# mbed_6LoWPAN_Border_Router_HAT.net
KiCad netlist of a schematic drawn in EAGLE
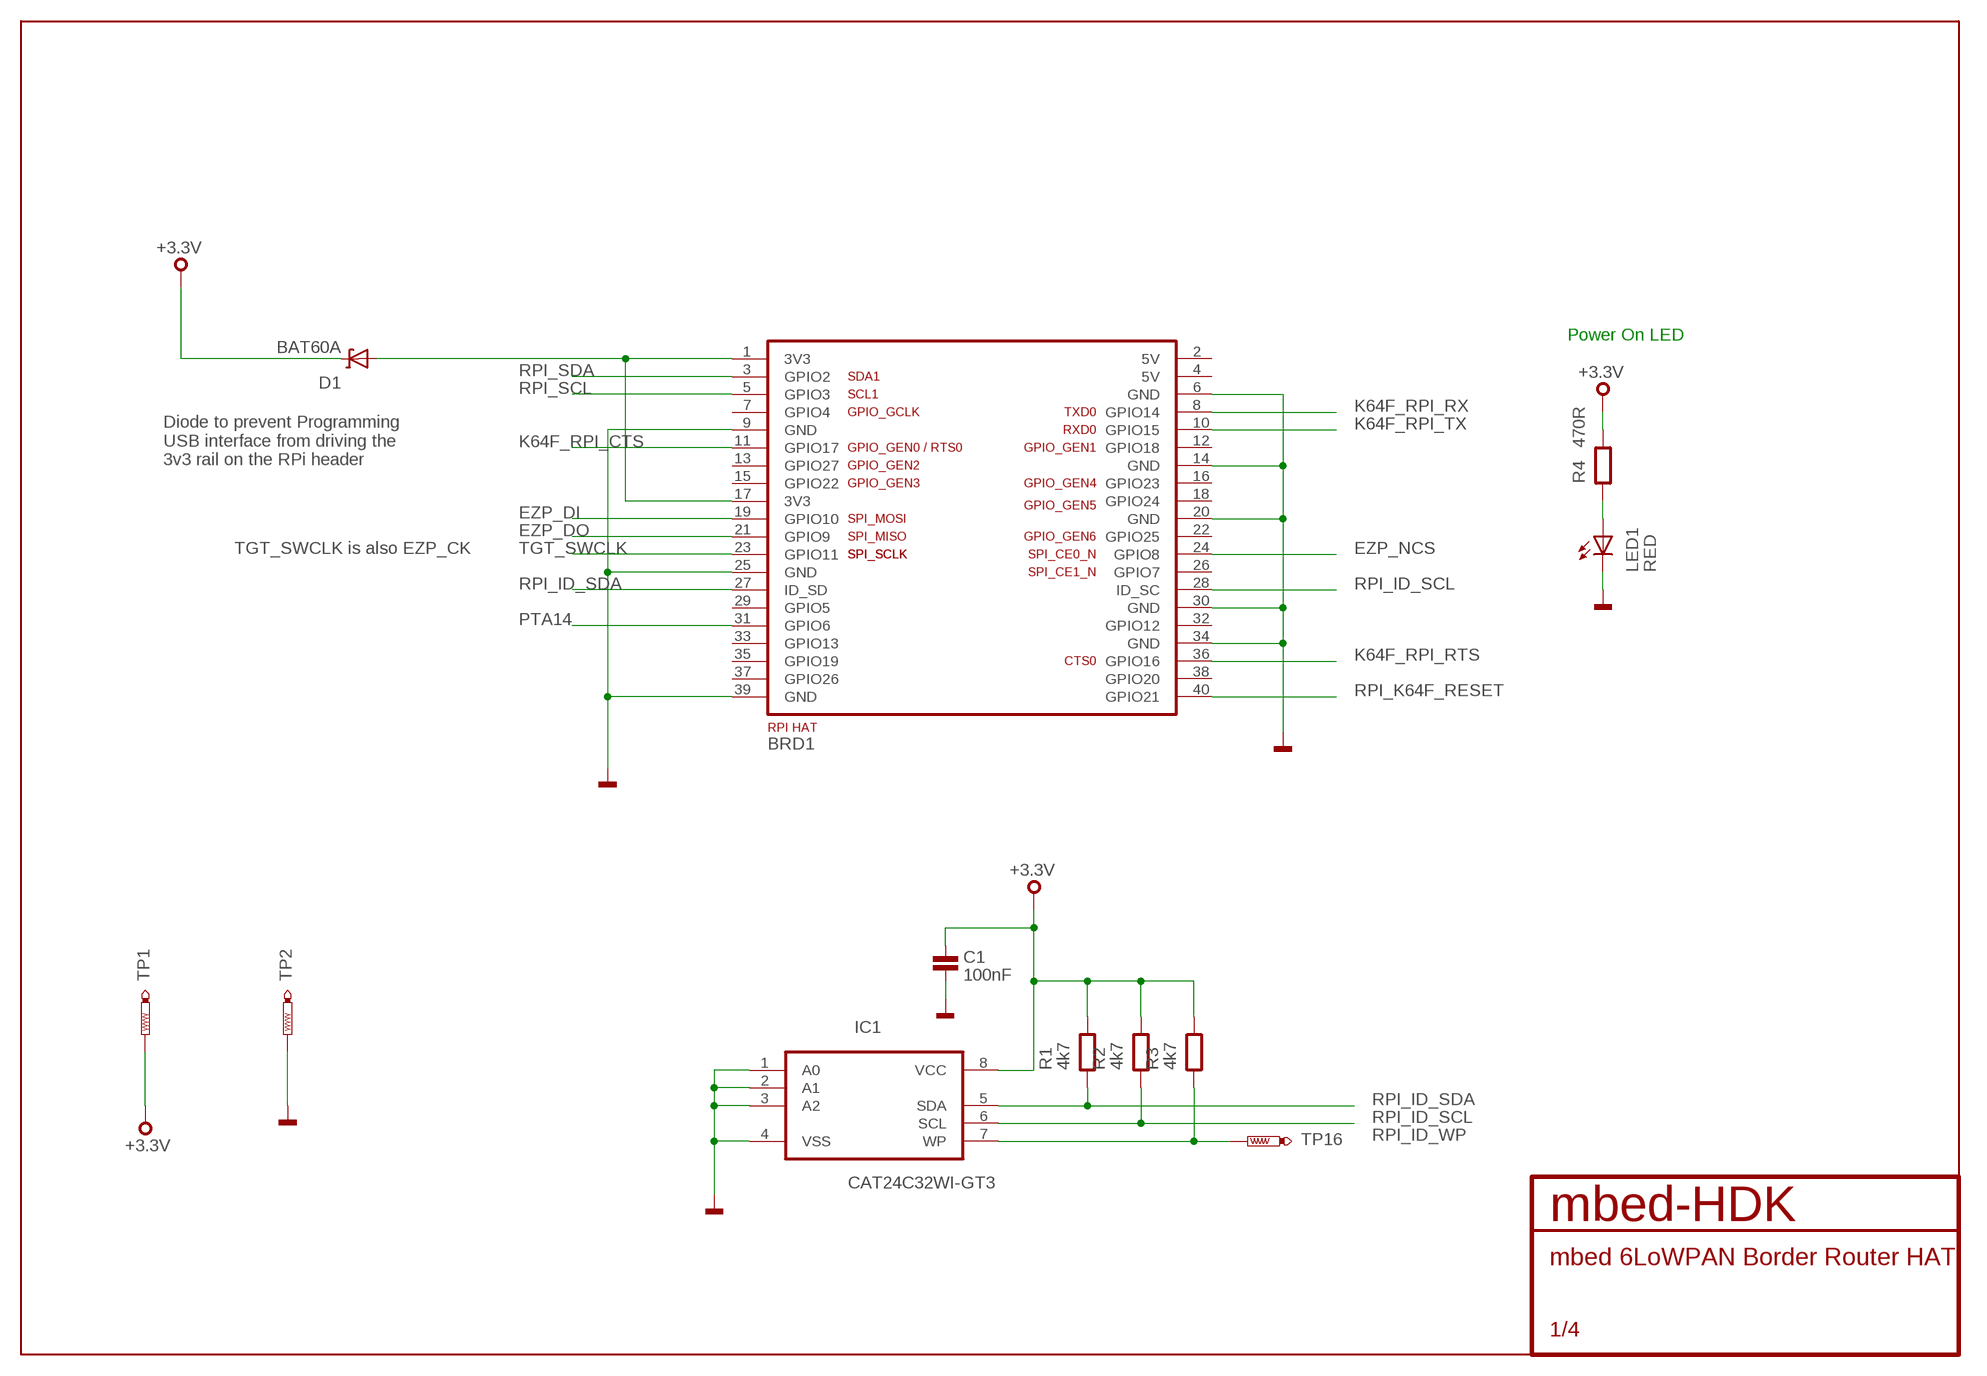
[diagram p0: schematic, sheet 1]
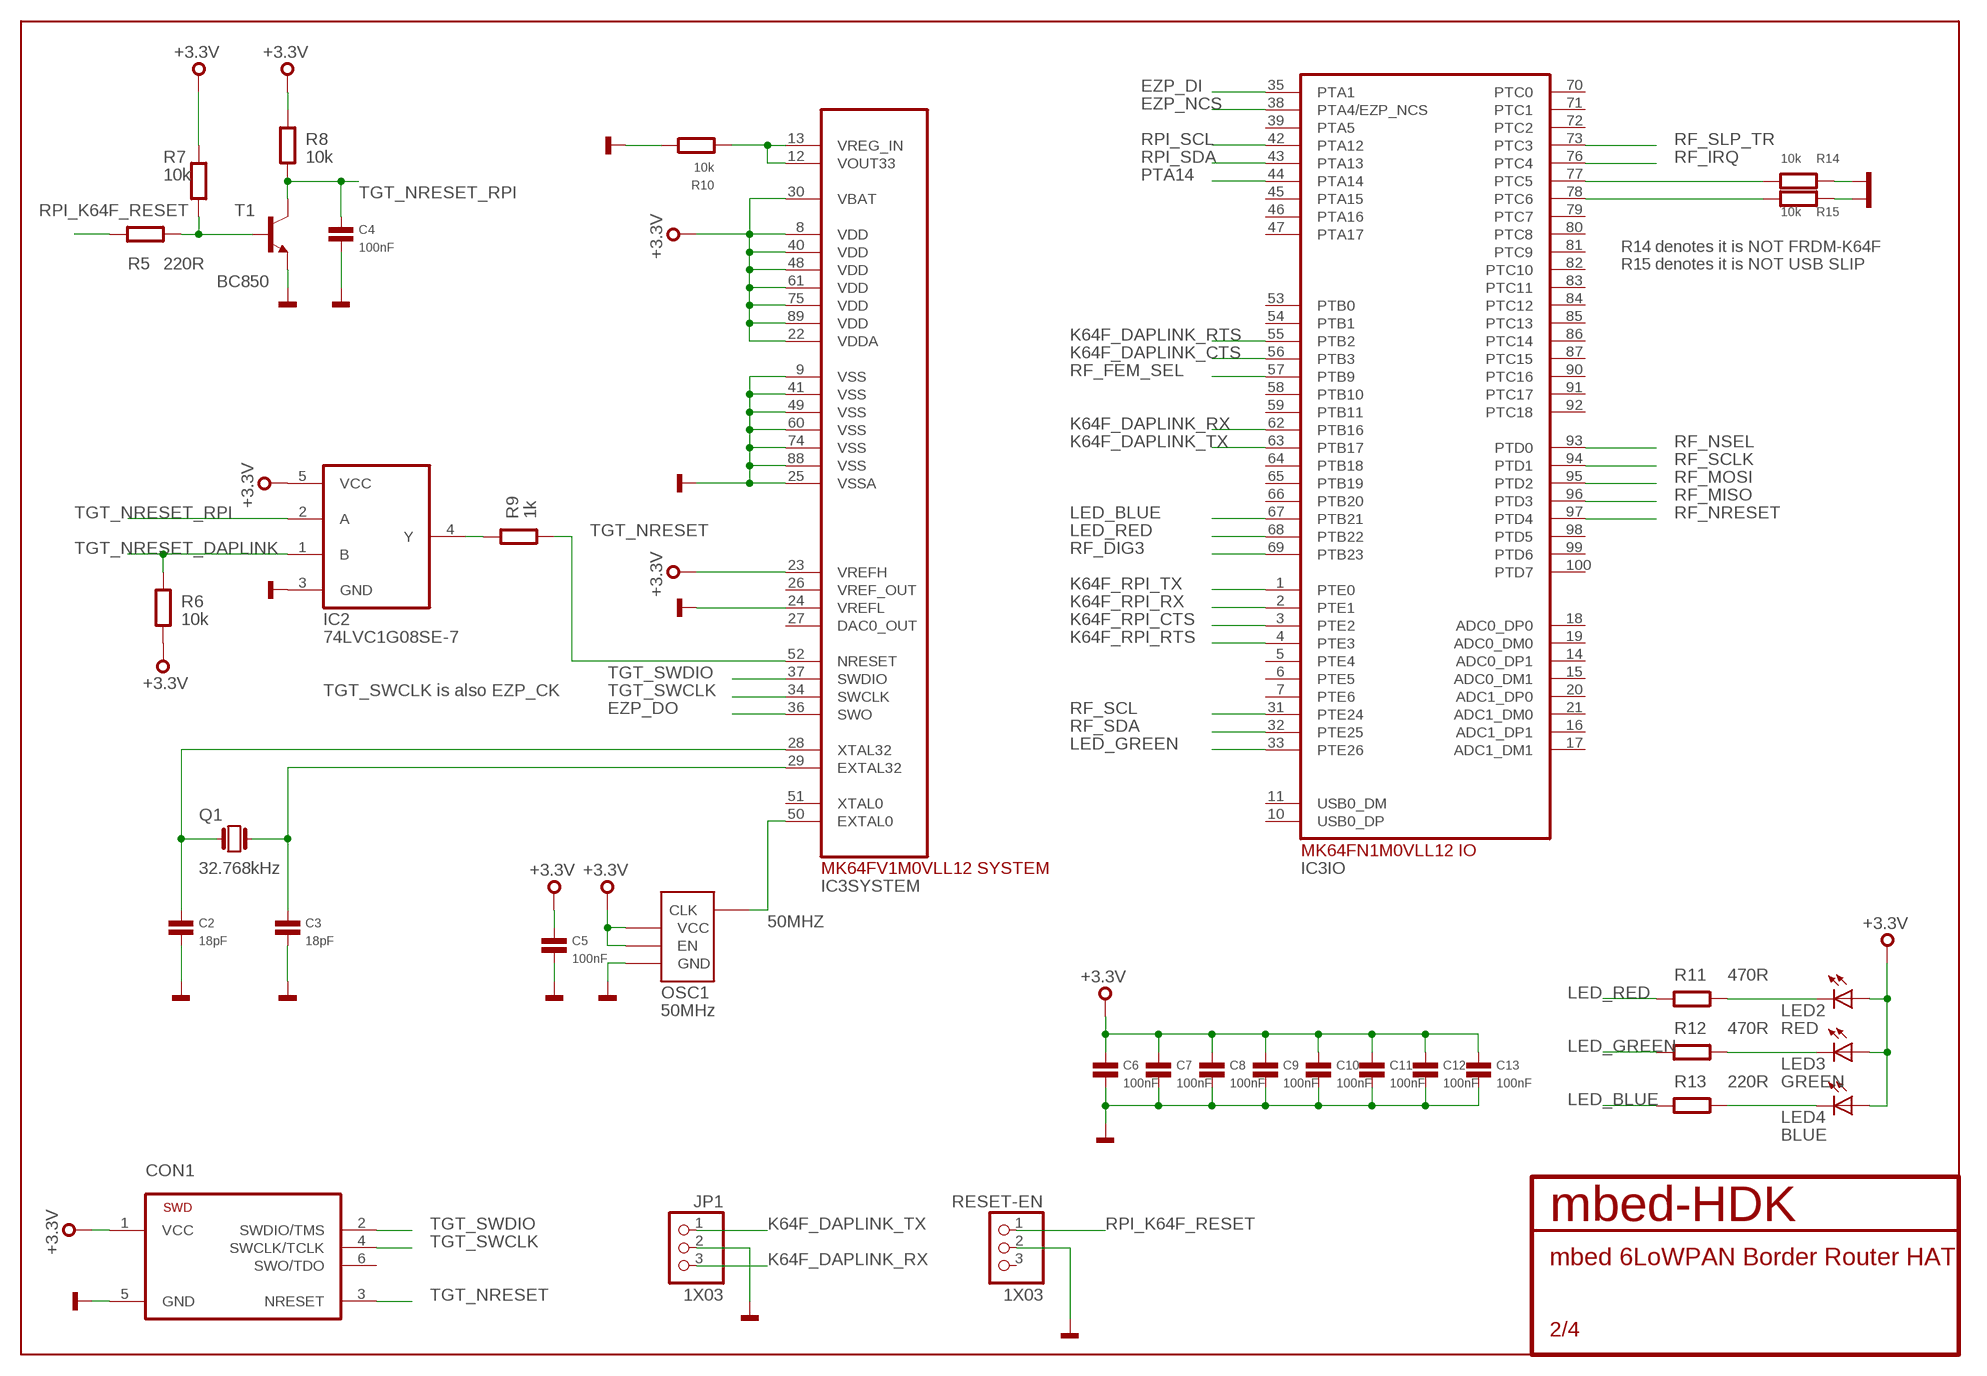
[diagram p1: schematic, sheet 2]
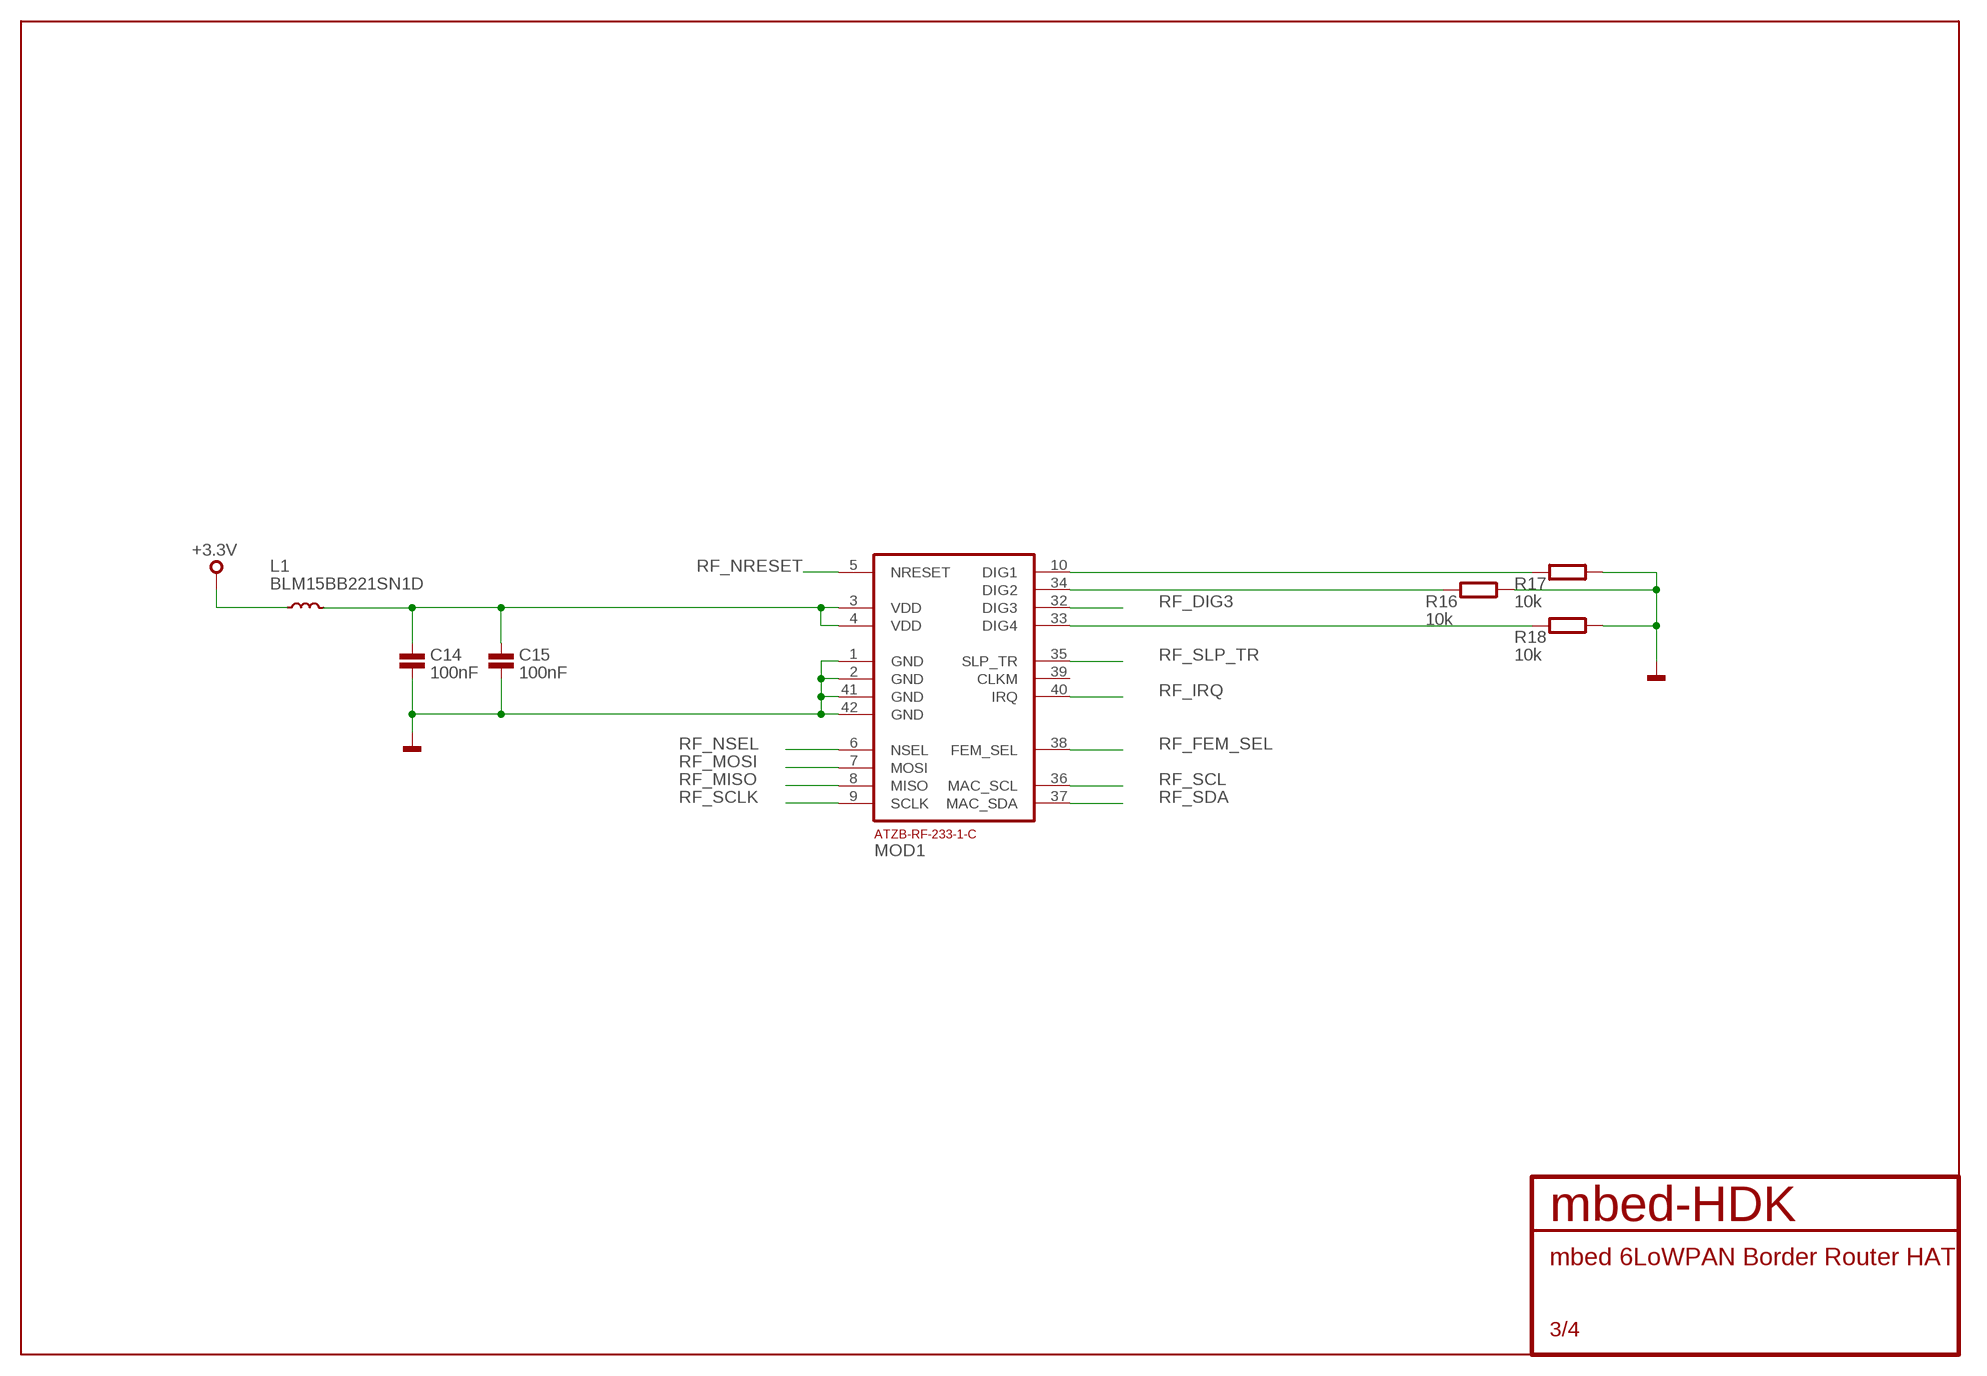
[diagram p2: schematic, sheet 3]
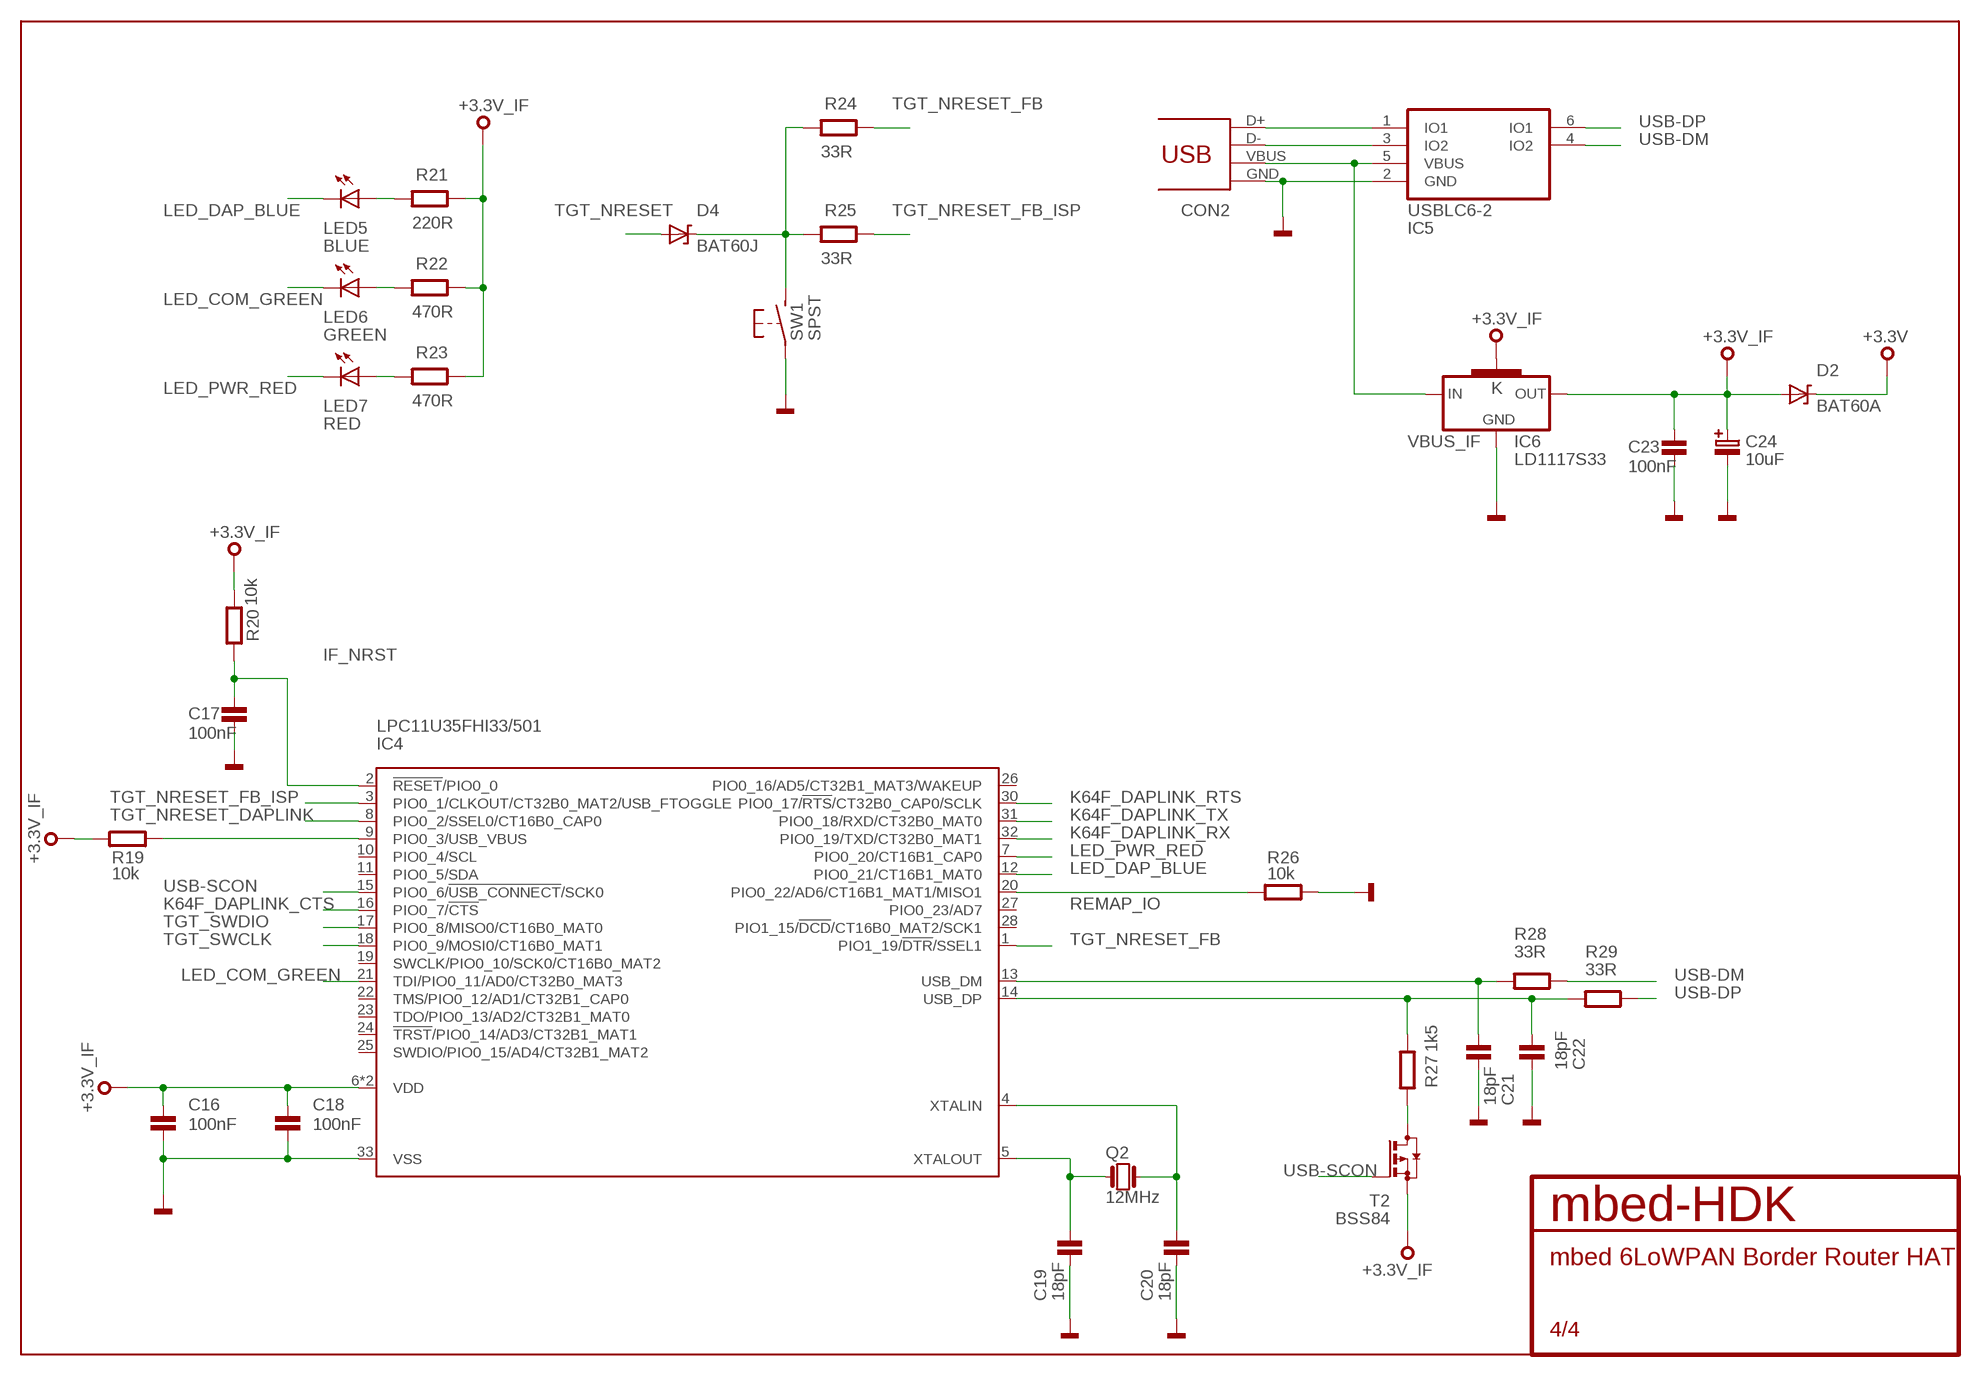
[diagram p3: schematic, sheet 4]

(export (version "E")
  (design (tool "Eeschema 10.0.6"))
  (components
    (comp (ref "C2")
      (value "18pF")
      (footprint "eagle-import:0402")
      (libsource (lib "eagle-import") (part "C0402"))
    )
    (comp (ref "C3")
      (value "18pF")
      (footprint "eagle-import:0402")
      (libsource (lib "eagle-import") (part "C0402"))
    )
    (comp (ref "C4")
      (value "100nF")
      (footprint "eagle-import:0402")
      (libsource (lib "eagle-import") (part "C0402"))
    )
    (comp (ref "C5")
      (value "100nF")
      (footprint "eagle-import:0402")
      (libsource (lib "eagle-import") (part "C0402"))
    )
    (comp (ref "C6")
      (value "100nF")
      (footprint "eagle-import:0402")
      (libsource (lib "eagle-import") (part "C0402"))
    )
    (comp (ref "C7")
      (value "100nF")
      (footprint "eagle-import:0402")
      (libsource (lib "eagle-import") (part "C0402"))
    )
    (comp (ref "C8")
      (value "100nF")
      (footprint "eagle-import:0402")
      (libsource (lib "eagle-import") (part "C0402"))
    )
    (comp (ref "C9")
      (value "100nF")
      (footprint "eagle-import:0402")
      (libsource (lib "eagle-import") (part "C0402"))
    )
    (comp (ref "C10")
      (value "100nF")
      (footprint "eagle-import:0402")
      (libsource (lib "eagle-import") (part "C0402"))
    )
    (comp (ref "C11")
      (value "100nF")
      (footprint "eagle-import:0402")
      (libsource (lib "eagle-import") (part "C0402"))
    )
    (comp (ref "C12")
      (value "100nF")
      (footprint "eagle-import:0402")
      (libsource (lib "eagle-import") (part "C0402"))
    )
    (comp (ref "C13")
      (value "100nF")
      (footprint "eagle-import:0402")
      (libsource (lib "eagle-import") (part "C0402"))
    )
    (comp (ref "CON1")
      (value "TC2030-CTX-NL")
      (footprint "eagle-import:TC2030-CTX-NL")
      (libsource (lib "eagle-import") (part "TC2030-CTX-NL"))
    )
    (comp (ref "IC2")
      (value "74LVC1G08SE-7")
      (footprint "eagle-import:SOT353")
      (fields (field (name "MF") "Diodes Inc."))
      (libsource (lib "eagle-import") (part "74LVC1GXX"))
    )
    (comp (ref "IC3")
      (value "MK64FN1M0VLL12")
      (footprint "eagle-import:LQFP100")
      (libsource (lib "eagle-import") (part "MK64FN1M0VLL12"))
    )
    (comp (ref "JP1")
      (value "1X03")
      (footprint "eagle-import:1X03")
      (libsource (lib "eagle-import") (part "PINHD-1X3"))
    )
    (comp (ref "LED2")
      (value "RED")
      (footprint "eagle-import:CHIPLED_0603")
      (libsource (lib "eagle-import") (part "LED0603"))
    )
    (comp (ref "LED3")
      (value "GREEN")
      (footprint "eagle-import:CHIPLED_0603")
      (libsource (lib "eagle-import") (part "LED0603"))
    )
    (comp (ref "LED4")
      (value "BLUE")
      (footprint "eagle-import:CHIPLED_0603")
      (libsource (lib "eagle-import") (part "LED0603"))
    )
    (comp (ref "OSC1")
      (value "50MHz")
      (footprint "eagle-import:3.2X.2.5")
      (libsource (lib "eagle-import") (part "OSCILLATOR3.2X2.5"))
    )
    (comp (ref "Q1")
      (value "32.768kHz")
      (footprint "eagle-import:FC135")
      (libsource (lib "eagle-import") (part "Q_FC135"))
    )
    (comp (ref "R5")
      (value "220R")
      (footprint "eagle-import:0402")
      (libsource (lib "eagle-import") (part "R0402"))
    )
    (comp (ref "R6")
      (value "10k")
      (footprint "eagle-import:0402")
      (libsource (lib "eagle-import") (part "R0402"))
    )
    (comp (ref "R7")
      (value "10k")
      (footprint "eagle-import:0402")
      (libsource (lib "eagle-import") (part "R0402"))
    )
    (comp (ref "R8")
      (value "10k")
      (footprint "eagle-import:0402")
      (libsource (lib "eagle-import") (part "R0402"))
    )
    (comp (ref "R9")
      (value "1k")
      (footprint "eagle-import:0402")
      (libsource (lib "eagle-import") (part "R0402"))
    )
    (comp (ref "R10")
      (value "10k")
      (footprint "eagle-import:0402")
      (libsource (lib "eagle-import") (part "R0402"))
    )
    (comp (ref "R11")
      (value "470R")
      (footprint "eagle-import:0402")
      (libsource (lib "eagle-import") (part "R0402"))
    )
    (comp (ref "R12")
      (value "470R")
      (footprint "eagle-import:0402")
      (libsource (lib "eagle-import") (part "R0402"))
    )
    (comp (ref "R13")
      (value "220R")
      (footprint "eagle-import:0402")
      (libsource (lib "eagle-import") (part "R0402"))
    )
    (comp (ref "R14")
      (value "10k")
      (footprint "eagle-import:0402")
      (libsource (lib "eagle-import") (part "R0402"))
    )
    (comp (ref "R15")
      (value "10k")
      (footprint "eagle-import:0402")
      (libsource (lib "eagle-import") (part "R0402"))
    )
    (comp (ref "RESET-EN")
      (value "1X03")
      (footprint "eagle-import:1X03")
      (libsource (lib "eagle-import") (part "PINHD-1X3"))
    )
    (comp (ref "T1")
      (value "BC850")
      (footprint "eagle-import:SOT23")
      (libsource (lib "eagle-import") (part "BC850"))
    )
    (comp (ref "BRD1")
      (value "RPI-HAT")
      (footprint "eagle-import:RPI-HAT")
      (libsource (lib "eagle-import") (part "RPI-HAT"))
    )
    (comp (ref "C1")
      (value "100nF")
      (footprint "eagle-import:0402")
      (libsource (lib "eagle-import") (part "C0402"))
    )
    (comp (ref "D1")
      (value "BAT60A")
      (footprint "eagle-import:SOD323")
      (fields (field (name "MF") "Infineon"))
      (libsource (lib "eagle-import") (part "BAT60A"))
    )
    (comp (ref "IC1")
      (value "CAT24C32WI-GT3")
      (footprint "eagle-import:SOIC127P600X175-8N")
      (libsource (lib "eagle-import") (part "CAT24C32WI-GT3"))
    )
    (comp (ref "LED1")
      (value "RED")
      (footprint "eagle-import:CHIPLED_0603")
      (libsource (lib "eagle-import") (part "LED0603"))
    )
    (comp (ref "R1")
      (value "4k7")
      (footprint "eagle-import:0402")
      (libsource (lib "eagle-import") (part "R0402"))
    )
    (comp (ref "R2")
      (value "4k7")
      (footprint "eagle-import:0402")
      (libsource (lib "eagle-import") (part "R0402"))
    )
    (comp (ref "R3")
      (value "4k7")
      (footprint "eagle-import:0402")
      (libsource (lib "eagle-import") (part "R0402"))
    )
    (comp (ref "R4")
      (value "470R")
      (footprint "eagle-import:0402")
      (libsource (lib "eagle-import") (part "R0402"))
    )
    (comp (ref "TP1")
      (value "TEST-POINT-50R-PTH")
      (footprint "eagle-import:TP50-PTH")
      (libsource (lib "eagle-import") (part "TEST-POINT-50R-PTH"))
    )
    (comp (ref "TP2")
      (value "TEST-POINT-50R-PTH")
      (footprint "eagle-import:TP50-PTH")
      (libsource (lib "eagle-import") (part "TEST-POINT-50R-PTH"))
    )
    (comp (ref "TP16")
      (value "TEST-POINT-50R-PTH")
      (footprint "eagle-import:TP50-PTH")
      (libsource (lib "eagle-import") (part "TEST-POINT-50R-PTH"))
    )
    (comp (ref "C14")
      (value "100nF")
      (footprint "eagle-import:0402")
      (libsource (lib "eagle-import") (part "C0402"))
    )
    (comp (ref "C15")
      (value "100nF")
      (footprint "eagle-import:0402")
      (libsource (lib "eagle-import") (part "C0402"))
    )
    (comp (ref "L1")
      (value "BLM15BB221SN1D")
      (footprint "eagle-import:0402")
      (libsource (lib "eagle-import") (part "L0402"))
    )
    (comp (ref "MOD1")
      (value "ATZB-RF-233-1-C")
      (footprint "eagle-import:ATZB-RF-233-1-C")
      (fields (field (name "MF") "Atmel"))
      (libsource (lib "eagle-import") (part "ATZB-RF-233-1-C"))
    )
    (comp (ref "R16")
      (value "10k")
      (footprint "eagle-import:0402")
      (libsource (lib "eagle-import") (part "R0402"))
    )
    (comp (ref "R17")
      (value "10k")
      (footprint "eagle-import:0402")
      (libsource (lib "eagle-import") (part "R0402"))
    )
    (comp (ref "R18")
      (value "10k")
      (footprint "eagle-import:0402")
      (libsource (lib "eagle-import") (part "R0402"))
    )
    (comp (ref "C16")
      (value "100nF")
      (footprint "eagle-import:0402")
      (libsource (lib "eagle-import") (part "C0402"))
    )
    (comp (ref "C17")
      (value "100nF")
      (footprint "eagle-import:0402")
      (libsource (lib "eagle-import") (part "C0402"))
    )
    (comp (ref "C18")
      (value "100nF")
      (footprint "eagle-import:0402")
      (libsource (lib "eagle-import") (part "C0402"))
    )
    (comp (ref "C19")
      (value "18pF")
      (footprint "eagle-import:0402")
      (libsource (lib "eagle-import") (part "C0402"))
    )
    (comp (ref "C20")
      (value "18pF")
      (footprint "eagle-import:0402")
      (libsource (lib "eagle-import") (part "C0402"))
    )
    (comp (ref "C21")
      (value "18pF")
      (footprint "eagle-import:0402")
      (libsource (lib "eagle-import") (part "C0402"))
    )
    (comp (ref "C22")
      (value "18pF")
      (footprint "eagle-import:0402")
      (libsource (lib "eagle-import") (part "C0402"))
    )
    (comp (ref "C23")
      (value "100nF")
      (footprint "eagle-import:0402")
      (libsource (lib "eagle-import") (part "C0402"))
    )
    (comp (ref "C24")
      (value "10uF")
      (footprint "eagle-import:SMC_B")
      (fields (field (name "MF") "Kemet"))
      (libsource (lib "eagle-import") (part "C-POLB"))
    )
    (comp (ref "CON2")
      (value "USB_MICROB")
      (footprint "eagle-import:MOLEX-47364-0001")
      (fields (field (name "MF") "MOLEX"))
      (libsource (lib "eagle-import") (part "USB_MICROB"))
    )
    (comp (ref "D2")
      (value "BAT60A")
      (footprint "eagle-import:SOD323")
      (fields (field (name "MF") "Infineon"))
      (libsource (lib "eagle-import") (part "BAT60A"))
    )
    (comp (ref "D4")
      (value "BAT60J")
      (footprint "eagle-import:SOD323")
      (fields (field (name "MF") "STMicroelectronics"))
      (libsource (lib "eagle-import") (part "BAT60J"))
    )
    (comp (ref "IC4")
      (value "LPC11U35FHI33/501")
      (footprint "eagle-import:SOT617-3")
      (fields (field (name "MF") "NXP Semiconductors"))
      (libsource (lib "eagle-import") (part "LPC11U35FHI33/501"))
    )
    (comp (ref "IC5")
      (value "USBLC6-2SC6")
      (footprint "eagle-import:SOT23-6L")
      (libsource (lib "eagle-import") (part "USBLC6-2SC6"))
    )
    (comp (ref "IC6")
      (value "LD1117S33")
      (footprint "eagle-import:SOT223")
      (libsource (lib "eagle-import") (part "LD1117S33"))
    )
    (comp (ref "LED5")
      (value "BLUE")
      (footprint "eagle-import:CHIPLED_0603")
      (libsource (lib "eagle-import") (part "LED0603"))
    )
    (comp (ref "LED6")
      (value "GREEN")
      (footprint "eagle-import:CHIPLED_0603")
      (libsource (lib "eagle-import") (part "LED0603"))
    )
    (comp (ref "LED7")
      (value "RED")
      (footprint "eagle-import:CHIPLED_0603")
      (libsource (lib "eagle-import") (part "LED0603"))
    )
    (comp (ref "Q2")
      (value "12MHz")
      (footprint "eagle-import:3.2X.2.5")
      (libsource (lib "eagle-import") (part "Q_3.2X2.5"))
    )
    (comp (ref "R19")
      (value "10k")
      (footprint "eagle-import:0402")
      (libsource (lib "eagle-import") (part "R0402"))
    )
    (comp (ref "R20")
      (value "10k")
      (footprint "eagle-import:0402")
      (libsource (lib "eagle-import") (part "R0402"))
    )
    (comp (ref "R21")
      (value "220R")
      (footprint "eagle-import:0402")
      (libsource (lib "eagle-import") (part "R0402"))
    )
    (comp (ref "R22")
      (value "470R")
      (footprint "eagle-import:0402")
      (libsource (lib "eagle-import") (part "R0402"))
    )
    (comp (ref "R23")
      (value "470R")
      (footprint "eagle-import:0402")
      (libsource (lib "eagle-import") (part "R0402"))
    )
    (comp (ref "R24")
      (value "33R")
      (footprint "eagle-import:0402")
      (libsource (lib "eagle-import") (part "R0402"))
    )
    (comp (ref "R25")
      (value "33R")
      (footprint "eagle-import:0402")
      (libsource (lib "eagle-import") (part "R0402"))
    )
    (comp (ref "R26")
      (value "10k")
      (footprint "eagle-import:0402")
      (libsource (lib "eagle-import") (part "R0402"))
    )
    (comp (ref "R27")
      (value "1k5")
      (footprint "eagle-import:0402")
      (libsource (lib "eagle-import") (part "R0402"))
    )
    (comp (ref "R28")
      (value "33R")
      (footprint "eagle-import:0402")
      (libsource (lib "eagle-import") (part "R0402"))
    )
    (comp (ref "R29")
      (value "33R")
      (footprint "eagle-import:0402")
      (libsource (lib "eagle-import") (part "R0402"))
    )
    (comp (ref "SW1")
      (value "SPST")
      (footprint "eagle-import:DTSM-32S-B")
      (libsource (lib "eagle-import") (part "SPST"))
    )
    (comp (ref "T2")
      (value "BSS84")
      (footprint "eagle-import:SOT23")
      (libsource (lib "eagle-import") (part "BSS84"))
    )
  )
  (nets
    (net (code "1") (name "+3.3V") (class "Default")
      (node (ref "C1") (pin "1") (pinfunction "P$1_1") (pintype "passive"))
      (node (ref "C10") (pin "1") (pinfunction "P$1_1") (pintype "passive"))
      (node (ref "C11") (pin "1") (pinfunction "P$1_1") (pintype "passive"))
      (node (ref "C12") (pin "1") (pinfunction "P$1_1") (pintype "passive"))
      (node (ref "C13") (pin "1") (pinfunction "P$1_1") (pintype "passive"))
      (node (ref "C5") (pin "1") (pinfunction "P$1_1") (pintype "passive"))
      (node (ref "C6") (pin "1") (pinfunction "P$1_1") (pintype "passive"))
      (node (ref "C7") (pin "1") (pinfunction "P$1_1") (pintype "passive"))
      (node (ref "C8") (pin "1") (pinfunction "P$1_1") (pintype "passive"))
      (node (ref "C9") (pin "1") (pinfunction "P$1_1") (pintype "passive"))
      (node (ref "CON1") (pin "1") (pinfunction "VCC_1") (pintype "passive"))
      (node (ref "D1") (pin "K") (pinfunction "K_K") (pintype "passive"))
      (node (ref "D2") (pin "K") (pinfunction "K_K") (pintype "passive"))
      (node (ref "IC1") (pin "8") (pinfunction "VCC_8") (pintype "passive"))
      (node (ref "IC2") (pin "5") (pinfunction "VCC_5") (pintype "bidirectional"))
      (node (ref "IC3") (pin "22") (pinfunction "VDDA_22") (pintype "bidirectional"))
      (node (ref "IC3") (pin "23") (pinfunction "VREFH_23") (pintype "bidirectional"))
      (node (ref "IC3") (pin "30") (pinfunction "VBAT_30") (pintype "bidirectional"))
      (node (ref "IC3") (pin "40") (pinfunction "VDD_40") (pintype "bidirectional"))
      (node (ref "IC3") (pin "48") (pinfunction "VDD_48") (pintype "bidirectional"))
      (node (ref "IC3") (pin "61") (pinfunction "VDD_61") (pintype "bidirectional"))
      (node (ref "IC3") (pin "75") (pinfunction "VDD_75") (pintype "bidirectional"))
      (node (ref "IC3") (pin "8") (pinfunction "VDD_8") (pintype "bidirectional"))
      (node (ref "IC3") (pin "89") (pinfunction "VDD_89") (pintype "bidirectional"))
      (node (ref "L1") (pin "1") (pinfunction "P$1_1") (pintype "bidirectional"))
      (node (ref "LED2") (pin "A") (pinfunction "A_A") (pintype "passive"))
      (node (ref "LED3") (pin "A") (pinfunction "A_A") (pintype "passive"))
      (node (ref "LED4") (pin "A") (pinfunction "A_A") (pintype "passive"))
      (node (ref "OSC1") (pin "P$1") (pinfunction "EN_P$1") (pintype "bidirectional"))
      (node (ref "OSC1") (pin "P$4") (pinfunction "VCC_P$4") (pintype "bidirectional"))
      (node (ref "R1") (pin "2") (pinfunction "P$2_2") (pintype "passive"))
      (node (ref "R2") (pin "2") (pinfunction "P$2_2") (pintype "passive"))
      (node (ref "R3") (pin "2") (pinfunction "P$2_2") (pintype "passive"))
      (node (ref "R4") (pin "2") (pinfunction "P$2_2") (pintype "passive"))
      (node (ref "R6") (pin "1") (pinfunction "P$1_1") (pintype "passive"))
      (node (ref "R7") (pin "1") (pinfunction "P$1_1") (pintype "passive"))
      (node (ref "R8") (pin "2") (pinfunction "P$2_2") (pintype "passive"))
      (node (ref "TP1") (pin "TP") (pinfunction "TP_TP") (pintype "input"))
    )
    (net (code "2") (name "+3.3V_IF") (class "Default")
      (node (ref "C16") (pin "1") (pinfunction "P$1_1") (pintype "passive"))
      (node (ref "C18") (pin "1") (pinfunction "P$1_1") (pintype "passive"))
      (node (ref "C23") (pin "1") (pinfunction "P$1_1") (pintype "passive"))
      (node (ref "C24") (pin "+") (pinfunction "+_+") (pintype "passive"))
      (node (ref "D2") (pin "A") (pinfunction "A_A") (pintype "passive"))
      (node (ref "IC4") (pin "29") (pinfunction "VDD_29") (pintype "passive"))
      (node (ref "IC4") (pin "6") (pinfunction "VDD_6") (pintype "passive"))
      (node (ref "IC6") (pin "2") (pinfunction "OUT_2") (pintype "passive"))
      (node (ref "IC6") (pin "4") (pinfunction "K_4") (pintype "passive"))
      (node (ref "R19") (pin "2") (pinfunction "P$2_2") (pintype "passive"))
      (node (ref "R20") (pin "2") (pinfunction "P$2_2") (pintype "passive"))
      (node (ref "R21") (pin "1") (pinfunction "P$1_1") (pintype "passive"))
      (node (ref "R22") (pin "1") (pinfunction "P$1_1") (pintype "passive"))
      (node (ref "R23") (pin "1") (pinfunction "P$1_1") (pintype "passive"))
      (node (ref "T2") (pin "2") (pinfunction "S_2") (pintype "passive"))
    )
    (net (code "3") (name "50MHZ") (class "Default")
      (node (ref "IC3") (pin "50") (pinfunction "EXTAL0_50") (pintype "bidirectional"))
      (node (ref "OSC1") (pin "P$3") (pinfunction "CLK_P$3") (pintype "bidirectional"))
    )
    (net (code "4") (name "EZP_DI") (class "Default")
      (node (ref "BRD1") (pin "19") (pinfunction "GPIO10_19") (pintype "bidirectional"))
      (node (ref "IC3") (pin "35") (pinfunction "PTA1_35") (pintype "bidirectional"))
    )
    (net (code "5") (name "EZP_DO") (class "Default")
      (node (ref "BRD1") (pin "21") (pinfunction "GPIO9_21") (pintype "bidirectional"))
      (node (ref "IC3") (pin "36") (pinfunction "SWO_36") (pintype "bidirectional"))
    )
    (net (code "6") (name "EZP_NCS") (class "Default")
      (node (ref "BRD1") (pin "24") (pinfunction "GPIO8_24") (pintype "bidirectional"))
      (node (ref "IC3") (pin "38") (pinfunction "PTA4/EZP_NCS_38") (pintype "bidirectional"))
    )
    (net (code "7") (name "GND") (class "Default")
      (node (ref "BRD1") (pin "14") (pinfunction "GND_14") (pintype "bidirectional"))
      (node (ref "BRD1") (pin "20") (pinfunction "GND_20") (pintype "bidirectional"))
      (node (ref "BRD1") (pin "25") (pinfunction "GND_25") (pintype "bidirectional"))
      (node (ref "BRD1") (pin "30") (pinfunction "GND_30") (pintype "bidirectional"))
      (node (ref "BRD1") (pin "34") (pinfunction "GND_34") (pintype "bidirectional"))
      (node (ref "BRD1") (pin "39") (pinfunction "GND_39") (pintype "bidirectional"))
      (node (ref "BRD1") (pin "6") (pinfunction "GND_6") (pintype "bidirectional"))
      (node (ref "BRD1") (pin "9") (pinfunction "GND_9") (pintype "bidirectional"))
      (node (ref "C1") (pin "2") (pinfunction "P$2_2") (pintype "passive"))
      (node (ref "C10") (pin "2") (pinfunction "P$2_2") (pintype "passive"))
      (node (ref "C11") (pin "2") (pinfunction "P$2_2") (pintype "passive"))
      (node (ref "C12") (pin "2") (pinfunction "P$2_2") (pintype "passive"))
      (node (ref "C13") (pin "2") (pinfunction "P$2_2") (pintype "passive"))
      (node (ref "C14") (pin "2") (pinfunction "P$2_2") (pintype "passive"))
      (node (ref "C15") (pin "2") (pinfunction "P$2_2") (pintype "passive"))
      (node (ref "C16") (pin "2") (pinfunction "P$2_2") (pintype "passive"))
      (node (ref "C17") (pin "2") (pinfunction "P$2_2") (pintype "passive"))
      (node (ref "C18") (pin "2") (pinfunction "P$2_2") (pintype "passive"))
      (node (ref "C19") (pin "2") (pinfunction "P$2_2") (pintype "passive"))
      (node (ref "C2") (pin "2") (pinfunction "P$2_2") (pintype "passive"))
      (node (ref "C20") (pin "2") (pinfunction "P$2_2") (pintype "passive"))
      (node (ref "C21") (pin "2") (pinfunction "P$2_2") (pintype "passive"))
      (node (ref "C22") (pin "2") (pinfunction "P$2_2") (pintype "passive"))
      (node (ref "C23") (pin "2") (pinfunction "P$2_2") (pintype "passive"))
      (node (ref "C24") (pin "-") (pinfunction "-_-") (pintype "passive"))
      (node (ref "C3") (pin "2") (pinfunction "P$2_2") (pintype "passive"))
      (node (ref "C4") (pin "2") (pinfunction "P$2_2") (pintype "passive"))
      (node (ref "C5") (pin "2") (pinfunction "P$2_2") (pintype "passive"))
      (node (ref "C6") (pin "2") (pinfunction "P$2_2") (pintype "passive"))
      (node (ref "C7") (pin "2") (pinfunction "P$2_2") (pintype "passive"))
      (node (ref "C8") (pin "2") (pinfunction "P$2_2") (pintype "passive"))
      (node (ref "C9") (pin "2") (pinfunction "P$2_2") (pintype "passive"))
      (node (ref "CON1") (pin "5") (pinfunction "GND_5") (pintype "passive"))
      (node (ref "CON2") (pin "GND") (pinfunction "GND_GND") (pintype "bidirectional"))
      (node (ref "IC1") (pin "1") (pinfunction "A0_1") (pintype "input"))
      (node (ref "IC1") (pin "2") (pinfunction "A1_2") (pintype "input"))
      (node (ref "IC1") (pin "3") (pinfunction "A2_3") (pintype "input"))
      (node (ref "IC1") (pin "4") (pinfunction "VSS_4") (pintype "passive"))
      (node (ref "IC2") (pin "3") (pinfunction "GND_3") (pintype "bidirectional"))
      (node (ref "IC3") (pin "24") (pinfunction "VREFL_24") (pintype "bidirectional"))
      (node (ref "IC3") (pin "25") (pinfunction "VSSA_25") (pintype "bidirectional"))
      (node (ref "IC3") (pin "41") (pinfunction "VSS_41") (pintype "bidirectional"))
      (node (ref "IC3") (pin "49") (pinfunction "VSS_49") (pintype "bidirectional"))
      (node (ref "IC3") (pin "60") (pinfunction "VSS_60") (pintype "bidirectional"))
      (node (ref "IC3") (pin "74") (pinfunction "VSS_74") (pintype "bidirectional"))
      (node (ref "IC3") (pin "88") (pinfunction "VSS_88") (pintype "bidirectional"))
      (node (ref "IC3") (pin "9") (pinfunction "VSS_9") (pintype "bidirectional"))
      (node (ref "IC4") (pin "33") (pinfunction "VSS_33") (pintype "passive"))
      (node (ref "IC5") (pin "2") (pinfunction "GND_2") (pintype "bidirectional"))
      (node (ref "IC6") (pin "1") (pinfunction "GND_1") (pintype "input"))
      (node (ref "JP1") (pin "2") (pinfunction "2_2") (pintype "passive"))
      (node (ref "LED1") (pin "C") (pinfunction "C_C") (pintype "passive"))
      (node (ref "MOD1") (pin "1") (pinfunction "GND_1") (pintype "bidirectional"))
      (node (ref "MOD1") (pin "2") (pinfunction "GND_2") (pintype "bidirectional"))
      (node (ref "MOD1") (pin "41") (pinfunction "GND_41") (pintype "bidirectional"))
      (node (ref "MOD1") (pin "42") (pinfunction "GND_42") (pintype "bidirectional"))
      (node (ref "OSC1") (pin "P$2") (pinfunction "GND_P$2") (pintype "bidirectional"))
      (node (ref "R10") (pin "2") (pinfunction "P$2_2") (pintype "passive"))
      (node (ref "R14") (pin "2") (pinfunction "P$2_2") (pintype "passive"))
      (node (ref "R15") (pin "2") (pinfunction "P$2_2") (pintype "passive"))
      (node (ref "R16") (pin "2") (pinfunction "P$2_2") (pintype "passive"))
      (node (ref "R17") (pin "2") (pinfunction "P$2_2") (pintype "passive"))
      (node (ref "R18") (pin "1") (pinfunction "P$1_1") (pintype "passive"))
      (node (ref "R26") (pin "1") (pinfunction "P$1_1") (pintype "passive"))
      (node (ref "RESET-EN") (pin "2") (pinfunction "2_2") (pintype "passive"))
      (node (ref "SW1") (pin "P$1") (pinfunction "P_P$1") (pintype "passive"))
      (node (ref "T1") (pin "2") (pinfunction "E_2") (pintype "passive"))
      (node (ref "TP2") (pin "TP") (pinfunction "TP_TP") (pintype "input"))
    )
    (net (code "8") (name "IF_NRST") (class "Default")
      (node (ref "C17") (pin "1") (pinfunction "P$1_1") (pintype "passive"))
      (node (ref "IC4") (pin "2") (pinfunction "~{RESET}/PIO0_0_2") (pintype "bidirectional"))
      (node (ref "R20") (pin "1") (pinfunction "P$1_1") (pintype "passive"))
    )
    (net (code "9") (name "K64F_DAPLINK_CTS") (class "Default")
      (node (ref "IC3") (pin "56") (pinfunction "PTB3_56") (pintype "bidirectional"))
      (node (ref "IC4") (pin "16") (pinfunction "PIO0_7/~{CTS}_16") (pintype "bidirectional"))
    )
    (net (code "10") (name "K64F_DAPLINK_RTS") (class "Default")
      (node (ref "IC3") (pin "55") (pinfunction "PTB2_55") (pintype "bidirectional"))
      (node (ref "IC4") (pin "30") (pinfunction "PIO0_17/~{RTS}/CT32B0_CAP0/SCLK_30") (pintype "bidirectional"))
    )
    (net (code "11") (name "K64F_DAPLINK_RX") (class "Default")
      (node (ref "IC3") (pin "62") (pinfunction "PTB16_62") (pintype "bidirectional"))
      (node (ref "IC4") (pin "32") (pinfunction "PIO0_19/TXD/CT32B0_MAT1_32") (pintype "bidirectional"))
      (node (ref "JP1") (pin "3") (pinfunction "3_3") (pintype "passive"))
    )
    (net (code "12") (name "K64F_DAPLINK_TX") (class "Default")
      (node (ref "IC3") (pin "63") (pinfunction "PTB17_63") (pintype "bidirectional"))
      (node (ref "IC4") (pin "31") (pinfunction "PIO0_18/RXD/CT32B0_MAT0_31") (pintype "bidirectional"))
      (node (ref "JP1") (pin "1") (pinfunction "1_1") (pintype "passive"))
    )
    (net (code "13") (name "K64F_RPI_CTS") (class "Default")
      (node (ref "BRD1") (pin "11") (pinfunction "GPIO17_11") (pintype "bidirectional"))
      (node (ref "IC3") (pin "3") (pinfunction "PTE2_3") (pintype "bidirectional"))
    )
    (net (code "14") (name "K64F_RPI_RTS") (class "Default")
      (node (ref "BRD1") (pin "36") (pinfunction "GPIO16_36") (pintype "bidirectional"))
      (node (ref "IC3") (pin "4") (pinfunction "PTE3_4") (pintype "bidirectional"))
    )
    (net (code "15") (name "K64F_RPI_RX") (class "Default")
      (node (ref "BRD1") (pin "8") (pinfunction "GPIO14_8") (pintype "bidirectional"))
      (node (ref "IC3") (pin "2") (pinfunction "PTE1_2") (pintype "bidirectional"))
    )
    (net (code "16") (name "K64F_RPI_TX") (class "Default")
      (node (ref "BRD1") (pin "10") (pinfunction "GPIO15_10") (pintype "bidirectional"))
      (node (ref "IC3") (pin "1") (pinfunction "PTE0_1") (pintype "bidirectional"))
    )
    (net (code "17") (name "LED_BLUE") (class "Default")
      (node (ref "IC3") (pin "67") (pinfunction "PTB21_67") (pintype "bidirectional"))
      (node (ref "R13") (pin "1") (pinfunction "P$1_1") (pintype "passive"))
    )
    (net (code "18") (name "LED_COM_GREEN") (class "Default")
      (node (ref "IC4") (pin "21") (pinfunction "TDI/PIO0_11/AD0/CT32B0_MAT3_21") (pintype "bidirectional"))
      (node (ref "LED6") (pin "C") (pinfunction "C_C") (pintype "passive"))
    )
    (net (code "19") (name "LED_DAP_BLUE") (class "Default")
      (node (ref "IC4") (pin "12") (pinfunction "PIO0_21/CT16B1_MAT0_12") (pintype "bidirectional"))
      (node (ref "LED5") (pin "C") (pinfunction "C_C") (pintype "passive"))
    )
    (net (code "20") (name "LED_GREEN") (class "Default")
      (node (ref "IC3") (pin "33") (pinfunction "PTE26_33") (pintype "bidirectional"))
      (node (ref "R12") (pin "1") (pinfunction "P$1_1") (pintype "passive"))
    )
    (net (code "21") (name "LED_PWR_RED") (class "Default")
      (node (ref "IC4") (pin "7") (pinfunction "PIO0_20/CT16B1_CAP0_7") (pintype "bidirectional"))
      (node (ref "LED7") (pin "C") (pinfunction "C_C") (pintype "passive"))
    )
    (net (code "22") (name "LED_RED") (class "Default")
      (node (ref "IC3") (pin "68") (pinfunction "PTB22_68") (pintype "bidirectional"))
      (node (ref "R11") (pin "1") (pinfunction "P$1_1") (pintype "passive"))
    )
    (net (code "23") (name "Net-(BRD1-3V3-Pad1)") (class "Default")
      (node (ref "BRD1") (pin "1") (pinfunction "3V3_1") (pintype "bidirectional"))
      (node (ref "BRD1") (pin "17") (pinfunction "3V3_17") (pintype "bidirectional"))
      (node (ref "D1") (pin "A") (pinfunction "A_A") (pintype "passive"))
    )
    (net (code "24") (name "Net-(C2-P$1)") (class "Default")
      (node (ref "C2") (pin "1") (pinfunction "P$1_1") (pintype "passive"))
      (node (ref "IC3") (pin "28") (pinfunction "XTAL32_28") (pintype "bidirectional"))
      (node (ref "Q1") (pin "X1") (pinfunction "1_X1") (pintype "passive"))
    )
    (net (code "25") (name "Net-(C3-P$1)") (class "Default")
      (node (ref "C3") (pin "1") (pinfunction "P$1_1") (pintype "passive"))
      (node (ref "IC3") (pin "29") (pinfunction "EXTAL32_29") (pintype "bidirectional"))
      (node (ref "Q1") (pin "X2") (pinfunction "2_X2") (pintype "passive"))
    )
    (net (code "26") (name "Net-(C14-P$1)") (class "Default")
      (node (ref "C14") (pin "1") (pinfunction "P$1_1") (pintype "passive"))
      (node (ref "C15") (pin "1") (pinfunction "P$1_1") (pintype "passive"))
      (node (ref "L1") (pin "2") (pinfunction "P$2_2") (pintype "bidirectional"))
      (node (ref "MOD1") (pin "3") (pinfunction "VDD_3") (pintype "bidirectional"))
      (node (ref "MOD1") (pin "4") (pinfunction "VDD_4") (pintype "bidirectional"))
    )
    (net (code "27") (name "Net-(C19-P$1)") (class "Default")
      (node (ref "C19") (pin "1") (pinfunction "P$1_1") (pintype "passive"))
      (node (ref "IC4") (pin "5") (pinfunction "XTALOUT_5") (pintype "output"))
      (node (ref "Q2") (pin "P$1") (pinfunction "1_P$1") (pintype "passive"))
    )
    (net (code "28") (name "Net-(C20-P$1)") (class "Default")
      (node (ref "C20") (pin "1") (pinfunction "P$1_1") (pintype "passive"))
      (node (ref "IC4") (pin "4") (pinfunction "XTALIN_4") (pintype "input"))
      (node (ref "Q2") (pin "P$3") (pinfunction "2_P$3") (pintype "passive"))
    )
    (net (code "29") (name "Net-(C21-P$1)") (class "Default")
      (node (ref "C21") (pin "1") (pinfunction "P$1_1") (pintype "passive"))
      (node (ref "IC4") (pin "13") (pinfunction "USB_DM_13") (pintype "bidirectional"))
      (node (ref "R28") (pin "2") (pinfunction "P$2_2") (pintype "passive"))
    )
    (net (code "30") (name "Net-(C22-P$1)") (class "Default")
      (node (ref "C22") (pin "1") (pinfunction "P$1_1") (pintype "passive"))
      (node (ref "IC4") (pin "14") (pinfunction "USB_DP_14") (pintype "bidirectional"))
      (node (ref "R27") (pin "2") (pinfunction "P$2_2") (pintype "passive"))
      (node (ref "R29") (pin "2") (pinfunction "P$2_2") (pintype "passive"))
    )
    (net (code "31") (name "Net-(CON2-PadD+)") (class "Default")
      (node (ref "CON2") (pin "D+") (pinfunction "D+_D+") (pintype "bidirectional"))
      (node (ref "IC5") (pin "1") (pinfunction "IO1_1") (pintype "bidirectional"))
    )
    (net (code "32") (name "Net-(CON2-PadD-)") (class "Default")
      (node (ref "CON2") (pin "D-") (pinfunction "D-_D-") (pintype "bidirectional"))
      (node (ref "IC5") (pin "3") (pinfunction "IO2_3") (pintype "bidirectional"))
    )
    (net (code "33") (name "Net-(IC2-Y)") (class "Default")
      (node (ref "IC2") (pin "4") (pinfunction "Y_4") (pintype "bidirectional"))
      (node (ref "R9") (pin "2") (pinfunction "P$2_2") (pintype "passive"))
    )
    (net (code "34") (name "Net-(IC3A-PTC5)") (class "Default")
      (node (ref "IC3") (pin "77") (pinfunction "PTC5_77") (pintype "bidirectional"))
      (node (ref "R14") (pin "1") (pinfunction "P$1_1") (pintype "passive"))
    )
    (net (code "35") (name "Net-(IC3A-PTC6)") (class "Default")
      (node (ref "IC3") (pin "78") (pinfunction "PTC6_78") (pintype "bidirectional"))
      (node (ref "R15") (pin "1") (pinfunction "P$1_1") (pintype "passive"))
    )
    (net (code "36") (name "Net-(IC3B-VOUT33)") (class "Default")
      (node (ref "IC3") (pin "12") (pinfunction "VOUT33_12") (pintype "bidirectional"))
      (node (ref "IC3") (pin "13") (pinfunction "VREG_IN_13") (pintype "bidirectional"))
      (node (ref "R10") (pin "1") (pinfunction "P$1_1") (pintype "passive"))
    )
    (net (code "37") (name "Net-(IC4-PIO0_3{slash}USB_VBUS)") (class "Default")
      (node (ref "IC4") (pin "9") (pinfunction "PIO0_3/USB_VBUS_9") (pintype "bidirectional"))
      (node (ref "R19") (pin "1") (pinfunction "P$1_1") (pintype "passive"))
    )
    (net (code "38") (name "Net-(MOD1-DIG1)") (class "Default")
      (node (ref "MOD1") (pin "10") (pinfunction "DIG1_10") (pintype "bidirectional"))
      (node (ref "R17") (pin "1") (pinfunction "P$1_1") (pintype "passive"))
    )
    (net (code "39") (name "Net-(MOD1-DIG2)") (class "Default")
      (node (ref "MOD1") (pin "34") (pinfunction "DIG2_34") (pintype "bidirectional"))
      (node (ref "R16") (pin "1") (pinfunction "P$1_1") (pintype "passive"))
    )
    (net (code "40") (name "Net-(MOD1-DIG4)") (class "Default")
      (node (ref "MOD1") (pin "33") (pinfunction "DIG4_33") (pintype "bidirectional"))
      (node (ref "R18") (pin "2") (pinfunction "P$2_2") (pintype "passive"))
    )
    (net (code "41") (name "Net-(R4-P$1)") (class "Default")
      (node (ref "LED1") (pin "A") (pinfunction "A_A") (pintype "passive"))
      (node (ref "R4") (pin "1") (pinfunction "P$1_1") (pintype "passive"))
    )
    (net (code "42") (name "Net-(R5-P$1)") (class "Default")
      (node (ref "R5") (pin "1") (pinfunction "P$1_1") (pintype "passive"))
      (node (ref "R7") (pin "2") (pinfunction "P$2_2") (pintype "passive"))
      (node (ref "T1") (pin "1") (pinfunction "B_1") (pintype "passive"))
    )
    (net (code "43") (name "Net-(R11-P$2)") (class "Default")
      (node (ref "LED2") (pin "C") (pinfunction "C_C") (pintype "passive"))
      (node (ref "R11") (pin "2") (pinfunction "P$2_2") (pintype "passive"))
    )
    (net (code "44") (name "Net-(R12-P$2)") (class "Default")
      (node (ref "LED3") (pin "C") (pinfunction "C_C") (pintype "passive"))
      (node (ref "R12") (pin "2") (pinfunction "P$2_2") (pintype "passive"))
    )
    (net (code "45") (name "Net-(R13-P$2)") (class "Default")
      (node (ref "LED4") (pin "C") (pinfunction "C_C") (pintype "passive"))
      (node (ref "R13") (pin "2") (pinfunction "P$2_2") (pintype "passive"))
    )
    (net (code "46") (name "Net-(R21-P$2)") (class "Default")
      (node (ref "LED5") (pin "A") (pinfunction "A_A") (pintype "passive"))
      (node (ref "R21") (pin "2") (pinfunction "P$2_2") (pintype "passive"))
    )
    (net (code "47") (name "Net-(R22-P$2)") (class "Default")
      (node (ref "LED6") (pin "A") (pinfunction "A_A") (pintype "passive"))
      (node (ref "R22") (pin "2") (pinfunction "P$2_2") (pintype "passive"))
    )
    (net (code "48") (name "Net-(R23-P$2)") (class "Default")
      (node (ref "LED7") (pin "A") (pinfunction "A_A") (pintype "passive"))
      (node (ref "R23") (pin "2") (pinfunction "P$2_2") (pintype "passive"))
    )
    (net (code "49") (name "Net-(R24-P$2)") (class "Default")
      (node (ref "D4") (pin "K") (pinfunction "K_K") (pintype "passive"))
      (node (ref "R24") (pin "2") (pinfunction "P$2_2") (pintype "passive"))
      (node (ref "R25") (pin "2") (pinfunction "P$2_2") (pintype "passive"))
      (node (ref "SW1") (pin "P$2") (pinfunction "S_P$2") (pintype "passive"))
    )
    (net (code "50") (name "Net-(R27-P$1)") (class "Default")
      (node (ref "R27") (pin "1") (pinfunction "P$1_1") (pintype "passive"))
      (node (ref "T2") (pin "3") (pinfunction "D_3") (pintype "passive"))
    )
    (net (code "51") (name "PTA14") (class "Default")
      (node (ref "BRD1") (pin "31") (pinfunction "GPIO6_31") (pintype "bidirectional"))
      (node (ref "IC3") (pin "44") (pinfunction "PTA14_44") (pintype "bidirectional"))
    )
    (net (code "52") (name "REMAP_IO") (class "Default")
      (node (ref "IC4") (pin "20") (pinfunction "PIO0_22/AD6/CT16B1_MAT1/MISO1_20") (pintype "bidirectional"))
      (node (ref "R26") (pin "2") (pinfunction "P$2_2") (pintype "passive"))
    )
    (net (code "53") (name "RF_DIG3") (class "Default")
      (node (ref "IC3") (pin "69") (pinfunction "PTB23_69") (pintype "bidirectional"))
      (node (ref "MOD1") (pin "32") (pinfunction "DIG3_32") (pintype "bidirectional"))
    )
    (net (code "54") (name "RF_FEM_SEL") (class "Default")
      (node (ref "IC3") (pin "57") (pinfunction "PTB9_57") (pintype "bidirectional"))
      (node (ref "MOD1") (pin "38") (pinfunction "FEM_SEL_38") (pintype "bidirectional"))
    )
    (net (code "55") (name "RF_IRQ") (class "Default")
      (node (ref "IC3") (pin "76") (pinfunction "PTC4_76") (pintype "bidirectional"))
      (node (ref "MOD1") (pin "40") (pinfunction "IRQ_40") (pintype "bidirectional"))
    )
    (net (code "56") (name "RF_MISO") (class "Default")
      (node (ref "IC3") (pin "96") (pinfunction "PTD3_96") (pintype "bidirectional"))
      (node (ref "MOD1") (pin "8") (pinfunction "MISO_8") (pintype "bidirectional"))
    )
    (net (code "57") (name "RF_MOSI") (class "Default")
      (node (ref "IC3") (pin "95") (pinfunction "PTD2_95") (pintype "bidirectional"))
      (node (ref "MOD1") (pin "7") (pinfunction "MOSI_7") (pintype "bidirectional"))
    )
    (net (code "58") (name "RF_NRESET") (class "Default")
      (node (ref "IC3") (pin "97") (pinfunction "PTD4_97") (pintype "bidirectional"))
      (node (ref "MOD1") (pin "5") (pinfunction "NRESET_5") (pintype "bidirectional"))
    )
    (net (code "59") (name "RF_NSEL") (class "Default")
      (node (ref "IC3") (pin "93") (pinfunction "PTD0_93") (pintype "bidirectional"))
      (node (ref "MOD1") (pin "6") (pinfunction "NSEL_6") (pintype "bidirectional"))
    )
    (net (code "60") (name "RF_SCL") (class "Default")
      (node (ref "IC3") (pin "31") (pinfunction "PTE24_31") (pintype "bidirectional"))
      (node (ref "MOD1") (pin "36") (pinfunction "MAC_SCL_36") (pintype "bidirectional"))
    )
    (net (code "61") (name "RF_SCLK") (class "Default")
      (node (ref "IC3") (pin "94") (pinfunction "PTD1_94") (pintype "bidirectional"))
      (node (ref "MOD1") (pin "9") (pinfunction "SCLK_9") (pintype "bidirectional"))
    )
    (net (code "62") (name "RF_SDA") (class "Default")
      (node (ref "IC3") (pin "32") (pinfunction "PTE25_32") (pintype "bidirectional"))
      (node (ref "MOD1") (pin "37") (pinfunction "MAC_SDA_37") (pintype "bidirectional"))
    )
    (net (code "63") (name "RF_SLP_TR") (class "Default")
      (node (ref "IC3") (pin "73") (pinfunction "PTC3_73") (pintype "bidirectional"))
      (node (ref "MOD1") (pin "35") (pinfunction "SLP_TR_35") (pintype "bidirectional"))
    )
    (net (code "64") (name "RPI_ID_SCL") (class "Default")
      (node (ref "BRD1") (pin "28") (pinfunction "ID_SC_28") (pintype "bidirectional"))
      (node (ref "IC1") (pin "6") (pinfunction "SCL_6") (pintype "input"))
      (node (ref "R2") (pin "1") (pinfunction "P$1_1") (pintype "passive"))
    )
    (net (code "65") (name "RPI_ID_SDA") (class "Default")
      (node (ref "BRD1") (pin "27") (pinfunction "ID_SD_27") (pintype "bidirectional"))
      (node (ref "IC1") (pin "5") (pinfunction "SDA_5") (pintype "bidirectional"))
      (node (ref "R1") (pin "1") (pinfunction "P$1_1") (pintype "passive"))
    )
    (net (code "66") (name "RPI_ID_WP") (class "Default")
      (node (ref "IC1") (pin "7") (pinfunction "WP_7") (pintype "input"))
      (node (ref "R3") (pin "1") (pinfunction "P$1_1") (pintype "passive"))
      (node (ref "TP16") (pin "TP") (pinfunction "TP_TP") (pintype "input"))
    )
    (net (code "67") (name "RPI_K64F_RESET") (class "Default")
      (node (ref "BRD1") (pin "40") (pinfunction "GPIO21_40") (pintype "bidirectional"))
      (node (ref "R5") (pin "2") (pinfunction "P$2_2") (pintype "passive"))
      (node (ref "RESET-EN") (pin "1") (pinfunction "1_1") (pintype "passive"))
    )
    (net (code "68") (name "RPI_SCL") (class "Default")
      (node (ref "BRD1") (pin "5") (pinfunction "GPIO3_5") (pintype "bidirectional"))
      (node (ref "IC3") (pin "42") (pinfunction "PTA12_42") (pintype "bidirectional"))
    )
    (net (code "69") (name "RPI_SDA") (class "Default")
      (node (ref "BRD1") (pin "3") (pinfunction "GPIO2_3") (pintype "bidirectional"))
      (node (ref "IC3") (pin "43") (pinfunction "PTA13_43") (pintype "bidirectional"))
    )
    (net (code "70") (name "TGT_NRESET") (class "Default")
      (node (ref "CON1") (pin "3") (pinfunction "NRESET_3") (pintype "passive"))
      (node (ref "D4") (pin "A") (pinfunction "A_A") (pintype "passive"))
      (node (ref "IC3") (pin "52") (pinfunction "NRESET_52") (pintype "bidirectional"))
      (node (ref "R9") (pin "1") (pinfunction "P$1_1") (pintype "passive"))
    )
    (net (code "71") (name "TGT_NRESET_DAPLINK") (class "Default")
      (node (ref "IC2") (pin "1") (pinfunction "B_1") (pintype "bidirectional"))
      (node (ref "IC4") (pin "8") (pinfunction "PIO0_2/SSEL0/CT16B0_CAP0_8") (pintype "bidirectional"))
      (node (ref "R6") (pin "2") (pinfunction "P$2_2") (pintype "passive"))
    )
    (net (code "72") (name "TGT_NRESET_FB") (class "Default")
      (node (ref "IC4") (pin "1") (pinfunction "PIO1_19/~{DTR}/SSEL1_1") (pintype "bidirectional"))
      (node (ref "R24") (pin "1") (pinfunction "P$1_1") (pintype "passive"))
    )
    (net (code "73") (name "TGT_NRESET_FB_ISP") (class "Default")
      (node (ref "IC4") (pin "3") (pinfunction "PIO0_1/CLKOUT/CT32B0_MAT2/USB_FTOGGLE_3") (pintype "bidirectional"))
      (node (ref "R25") (pin "1") (pinfunction "P$1_1") (pintype "passive"))
    )
    (net (code "74") (name "TGT_NRESET_RPI") (class "Default")
      (node (ref "C4") (pin "1") (pinfunction "P$1_1") (pintype "passive"))
      (node (ref "IC2") (pin "2") (pinfunction "A_2") (pintype "bidirectional"))
      (node (ref "R8") (pin "1") (pinfunction "P$1_1") (pintype "passive"))
      (node (ref "T1") (pin "3") (pinfunction "C_3") (pintype "passive"))
    )
    (net (code "75") (name "TGT_SWCLK") (class "Default")
      (node (ref "BRD1") (pin "23") (pinfunction "GPIO11_23") (pintype "bidirectional"))
      (node (ref "CON1") (pin "4") (pinfunction "SWCLK/TCLK_4") (pintype "passive"))
      (node (ref "IC3") (pin "34") (pinfunction "SWCLK_34") (pintype "bidirectional"))
      (node (ref "IC4") (pin "18") (pinfunction "PIO0_9/MOSI0/CT16B0_MAT1_18") (pintype "bidirectional"))
    )
    (net (code "76") (name "TGT_SWDIO") (class "Default")
      (node (ref "CON1") (pin "2") (pinfunction "SWDIO/TMS_2") (pintype "passive"))
      (node (ref "IC3") (pin "37") (pinfunction "SWDIO_37") (pintype "bidirectional"))
      (node (ref "IC4") (pin "17") (pinfunction "PIO0_8/MISO0/CT16B0_MAT0_17") (pintype "bidirectional"))
    )
    (net (code "77") (name "USB-DM") (class "Default")
      (node (ref "IC5") (pin "4") (pinfunction "IO2_4") (pintype "bidirectional"))
      (node (ref "R28") (pin "1") (pinfunction "P$1_1") (pintype "passive"))
    )
    (net (code "78") (name "USB-DP") (class "Default")
      (node (ref "IC5") (pin "6") (pinfunction "IO1_6") (pintype "bidirectional"))
      (node (ref "R29") (pin "1") (pinfunction "P$1_1") (pintype "passive"))
    )
    (net (code "79") (name "USB-SCON") (class "Default")
      (node (ref "IC4") (pin "15") (pinfunction "PIO0_6/~{USB_CONNECT}/SCK0_15") (pintype "bidirectional"))
      (node (ref "T2") (pin "1") (pinfunction "G_1") (pintype "passive"))
    )
    (net (code "80") (name "VBUS_IF") (class "Default")
      (node (ref "CON2") (pin "VBUS") (pinfunction "VBUS_VBUS") (pintype "bidirectional"))
      (node (ref "IC5") (pin "5") (pinfunction "VBUS_5") (pintype "bidirectional"))
      (node (ref "IC6") (pin "3") (pinfunction "IN_3") (pintype "input"))
    )
    (net (code "81") (name "unconnected-(BRD1-5V-Pad2)") (class "Default")
      (node (ref "BRD1") (pin "2") (pinfunction "5V_2") (pintype "bidirectional"))
    )
    (net (code "82") (name "unconnected-(BRD1-5V-Pad4)") (class "Default")
      (node (ref "BRD1") (pin "4") (pinfunction "5V_4") (pintype "bidirectional"))
    )
    (net (code "83") (name "unconnected-(BRD1-GPIO4-Pad7)") (class "Default")
      (node (ref "BRD1") (pin "7") (pinfunction "GPIO4_7") (pintype "bidirectional"))
    )
    (net (code "84") (name "unconnected-(BRD1-GPIO5-Pad29)") (class "Default")
      (node (ref "BRD1") (pin "29") (pinfunction "GPIO5_29") (pintype "bidirectional"))
    )
    (net (code "85") (name "unconnected-(BRD1-GPIO7-Pad26)") (class "Default")
      (node (ref "BRD1") (pin "26") (pinfunction "GPIO7_26") (pintype "bidirectional"))
    )
    (net (code "86") (name "unconnected-(BRD1-GPIO12-Pad32)") (class "Default")
      (node (ref "BRD1") (pin "32") (pinfunction "GPIO12_32") (pintype "bidirectional"))
    )
    (net (code "87") (name "unconnected-(BRD1-GPIO13-Pad33)") (class "Default")
      (node (ref "BRD1") (pin "33") (pinfunction "GPIO13_33") (pintype "bidirectional"))
    )
    (net (code "88") (name "unconnected-(BRD1-GPIO18-Pad12)") (class "Default")
      (node (ref "BRD1") (pin "12") (pinfunction "GPIO18_12") (pintype "bidirectional"))
    )
    (net (code "89") (name "unconnected-(BRD1-GPIO19-Pad35)") (class "Default")
      (node (ref "BRD1") (pin "35") (pinfunction "GPIO19_35") (pintype "bidirectional"))
    )
    (net (code "90") (name "unconnected-(BRD1-GPIO20-Pad38)") (class "Default")
      (node (ref "BRD1") (pin "38") (pinfunction "GPIO20_38") (pintype "bidirectional"))
    )
    (net (code "91") (name "unconnected-(BRD1-GPIO22-Pad15)") (class "Default")
      (node (ref "BRD1") (pin "15") (pinfunction "GPIO22_15") (pintype "bidirectional"))
    )
    (net (code "92") (name "unconnected-(BRD1-GPIO23-Pad16)") (class "Default")
      (node (ref "BRD1") (pin "16") (pinfunction "GPIO23_16") (pintype "bidirectional"))
    )
    (net (code "93") (name "unconnected-(BRD1-GPIO24-Pad18)") (class "Default")
      (node (ref "BRD1") (pin "18") (pinfunction "GPIO24_18") (pintype "bidirectional"))
    )
    (net (code "94") (name "unconnected-(BRD1-GPIO25-Pad22)") (class "Default")
      (node (ref "BRD1") (pin "22") (pinfunction "GPIO25_22") (pintype "bidirectional"))
    )
    (net (code "95") (name "unconnected-(BRD1-GPIO26-Pad37)") (class "Default")
      (node (ref "BRD1") (pin "37") (pinfunction "GPIO26_37") (pintype "bidirectional"))
    )
    (net (code "96") (name "unconnected-(BRD1-GPIO27-Pad13)") (class "Default")
      (node (ref "BRD1") (pin "13") (pinfunction "GPIO27_13") (pintype "bidirectional"))
    )
    (net (code "97") (name "unconnected-(CON1-SWO{slash}TDO-Pad6)") (class "Default")
      (node (ref "CON1") (pin "6") (pinfunction "SWO/TDO_6") (pintype "passive"))
    )
    (net (code "98") (name "unconnected-(IC3A-ADC0_DM0-Pad19)") (class "Default")
      (node (ref "IC3") (pin "19") (pinfunction "ADC0_DM0_19") (pintype "bidirectional"))
    )
    (net (code "99") (name "unconnected-(IC3A-ADC0_DM1-Pad15)") (class "Default")
      (node (ref "IC3") (pin "15") (pinfunction "ADC0_DM1_15") (pintype "bidirectional"))
    )
    (net (code "100") (name "unconnected-(IC3A-ADC0_DP0-Pad18)") (class "Default")
      (node (ref "IC3") (pin "18") (pinfunction "ADC0_DP0_18") (pintype "bidirectional"))
    )
    (net (code "101") (name "unconnected-(IC3A-ADC0_DP1-Pad14)") (class "Default")
      (node (ref "IC3") (pin "14") (pinfunction "ADC0_DP1_14") (pintype "bidirectional"))
    )
    (net (code "102") (name "unconnected-(IC3A-ADC1_DM0-Pad21)") (class "Default")
      (node (ref "IC3") (pin "21") (pinfunction "ADC1_DM0_21") (pintype "bidirectional"))
    )
    (net (code "103") (name "unconnected-(IC3A-ADC1_DM1-Pad17)") (class "Default")
      (node (ref "IC3") (pin "17") (pinfunction "ADC1_DM1_17") (pintype "bidirectional"))
    )
    (net (code "104") (name "unconnected-(IC3A-ADC1_DP0-Pad20)") (class "Default")
      (node (ref "IC3") (pin "20") (pinfunction "ADC1_DP0_20") (pintype "bidirectional"))
    )
    (net (code "105") (name "unconnected-(IC3A-ADC1_DP1-Pad16)") (class "Default")
      (node (ref "IC3") (pin "16") (pinfunction "ADC1_DP1_16") (pintype "bidirectional"))
    )
    (net (code "106") (name "unconnected-(IC3A-PTA5-Pad39)") (class "Default")
      (node (ref "IC3") (pin "39") (pinfunction "PTA5_39") (pintype "bidirectional"))
    )
    (net (code "107") (name "unconnected-(IC3A-PTA15-Pad45)") (class "Default")
      (node (ref "IC3") (pin "45") (pinfunction "PTA15_45") (pintype "bidirectional"))
    )
    (net (code "108") (name "unconnected-(IC3A-PTA16-Pad46)") (class "Default")
      (node (ref "IC3") (pin "46") (pinfunction "PTA16_46") (pintype "bidirectional"))
    )
    (net (code "109") (name "unconnected-(IC3A-PTA17-Pad47)") (class "Default")
      (node (ref "IC3") (pin "47") (pinfunction "PTA17_47") (pintype "bidirectional"))
    )
    (net (code "110") (name "unconnected-(IC3A-PTB0-Pad53)") (class "Default")
      (node (ref "IC3") (pin "53") (pinfunction "PTB0_53") (pintype "bidirectional"))
    )
    (net (code "111") (name "unconnected-(IC3A-PTB1-Pad54)") (class "Default")
      (node (ref "IC3") (pin "54") (pinfunction "PTB1_54") (pintype "bidirectional"))
    )
    (net (code "112") (name "unconnected-(IC3A-PTB10-Pad58)") (class "Default")
      (node (ref "IC3") (pin "58") (pinfunction "PTB10_58") (pintype "bidirectional"))
    )
    (net (code "113") (name "unconnected-(IC3A-PTB11-Pad59)") (class "Default")
      (node (ref "IC3") (pin "59") (pinfunction "PTB11_59") (pintype "bidirectional"))
    )
    (net (code "114") (name "unconnected-(IC3A-PTB18-Pad64)") (class "Default")
      (node (ref "IC3") (pin "64") (pinfunction "PTB18_64") (pintype "bidirectional"))
    )
    (net (code "115") (name "unconnected-(IC3A-PTB19-Pad65)") (class "Default")
      (node (ref "IC3") (pin "65") (pinfunction "PTB19_65") (pintype "bidirectional"))
    )
    (net (code "116") (name "unconnected-(IC3A-PTB20-Pad66)") (class "Default")
      (node (ref "IC3") (pin "66") (pinfunction "PTB20_66") (pintype "bidirectional"))
    )
    (net (code "117") (name "unconnected-(IC3A-PTC0-Pad70)") (class "Default")
      (node (ref "IC3") (pin "70") (pinfunction "PTC0_70") (pintype "bidirectional"))
    )
    (net (code "118") (name "unconnected-(IC3A-PTC1-Pad71)") (class "Default")
      (node (ref "IC3") (pin "71") (pinfunction "PTC1_71") (pintype "bidirectional"))
    )
    (net (code "119") (name "unconnected-(IC3A-PTC2-Pad72)") (class "Default")
      (node (ref "IC3") (pin "72") (pinfunction "PTC2_72") (pintype "bidirectional"))
    )
    (net (code "120") (name "unconnected-(IC3A-PTC7-Pad79)") (class "Default")
      (node (ref "IC3") (pin "79") (pinfunction "PTC7_79") (pintype "bidirectional"))
    )
    (net (code "121") (name "unconnected-(IC3A-PTC8-Pad80)") (class "Default")
      (node (ref "IC3") (pin "80") (pinfunction "PTC8_80") (pintype "bidirectional"))
    )
    (net (code "122") (name "unconnected-(IC3A-PTC9-Pad81)") (class "Default")
      (node (ref "IC3") (pin "81") (pinfunction "PTC9_81") (pintype "bidirectional"))
    )
    (net (code "123") (name "unconnected-(IC3A-PTC10-Pad82)") (class "Default")
      (node (ref "IC3") (pin "82") (pinfunction "PTC10_82") (pintype "bidirectional"))
    )
    (net (code "124") (name "unconnected-(IC3A-PTC11-Pad83)") (class "Default")
      (node (ref "IC3") (pin "83") (pinfunction "PTC11_83") (pintype "bidirectional"))
    )
    (net (code "125") (name "unconnected-(IC3A-PTC12-Pad84)") (class "Default")
      (node (ref "IC3") (pin "84") (pinfunction "PTC12_84") (pintype "bidirectional"))
    )
    (net (code "126") (name "unconnected-(IC3A-PTC13-Pad85)") (class "Default")
      (node (ref "IC3") (pin "85") (pinfunction "PTC13_85") (pintype "bidirectional"))
    )
    (net (code "127") (name "unconnected-(IC3A-PTC14-Pad86)") (class "Default")
      (node (ref "IC3") (pin "86") (pinfunction "PTC14_86") (pintype "bidirectional"))
    )
    (net (code "128") (name "unconnected-(IC3A-PTC15-Pad87)") (class "Default")
      (node (ref "IC3") (pin "87") (pinfunction "PTC15_87") (pintype "bidirectional"))
    )
    (net (code "129") (name "unconnected-(IC3A-PTC16-Pad90)") (class "Default")
      (node (ref "IC3") (pin "90") (pinfunction "PTC16_90") (pintype "bidirectional"))
    )
    (net (code "130") (name "unconnected-(IC3A-PTC17-Pad91)") (class "Default")
      (node (ref "IC3") (pin "91") (pinfunction "PTC17_91") (pintype "bidirectional"))
    )
    (net (code "131") (name "unconnected-(IC3A-PTC18-Pad92)") (class "Default")
      (node (ref "IC3") (pin "92") (pinfunction "PTC18_92") (pintype "bidirectional"))
    )
    (net (code "132") (name "unconnected-(IC3A-PTD5-Pad98)") (class "Default")
      (node (ref "IC3") (pin "98") (pinfunction "PTD5_98") (pintype "bidirectional"))
    )
    (net (code "133") (name "unconnected-(IC3A-PTD6-Pad99)") (class "Default")
      (node (ref "IC3") (pin "99") (pinfunction "PTD6_99") (pintype "bidirectional"))
    )
    (net (code "134") (name "unconnected-(IC3A-PTD7-Pad100)") (class "Default")
      (node (ref "IC3") (pin "100") (pinfunction "PTD7_100") (pintype "bidirectional"))
    )
    (net (code "135") (name "unconnected-(IC3A-PTE4-Pad5)") (class "Default")
      (node (ref "IC3") (pin "5") (pinfunction "PTE4_5") (pintype "bidirectional"))
    )
    (net (code "136") (name "unconnected-(IC3A-PTE5-Pad6)") (class "Default")
      (node (ref "IC3") (pin "6") (pinfunction "PTE5_6") (pintype "bidirectional"))
    )
    (net (code "137") (name "unconnected-(IC3A-PTE6-Pad7)") (class "Default")
      (node (ref "IC3") (pin "7") (pinfunction "PTE6_7") (pintype "bidirectional"))
    )
    (net (code "138") (name "unconnected-(IC3A-USB0_DM-Pad11)") (class "Default")
      (node (ref "IC3") (pin "11") (pinfunction "USB0_DM_11") (pintype "bidirectional"))
    )
    (net (code "139") (name "unconnected-(IC3A-USB0_DP-Pad10)") (class "Default")
      (node (ref "IC3") (pin "10") (pinfunction "USB0_DP_10") (pintype "bidirectional"))
    )
    (net (code "140") (name "unconnected-(IC3B-DAC0_OUT-Pad27)") (class "Default")
      (node (ref "IC3") (pin "27") (pinfunction "DAC0_OUT_27") (pintype "bidirectional"))
    )
    (net (code "141") (name "unconnected-(IC3B-VREF_OUT-Pad26)") (class "Default")
      (node (ref "IC3") (pin "26") (pinfunction "VREF_OUT_26") (pintype "bidirectional"))
    )
    (net (code "142") (name "unconnected-(IC3B-XTAL0-Pad51)") (class "Default")
      (node (ref "IC3") (pin "51") (pinfunction "XTAL0_51") (pintype "bidirectional"))
    )
    (net (code "143") (name "unconnected-(IC4-PIO0_4{slash}SCL-Pad10)") (class "Default")
      (node (ref "IC4") (pin "10") (pinfunction "PIO0_4/SCL_10") (pintype "bidirectional"))
    )
    (net (code "144") (name "unconnected-(IC4-PIO0_5{slash}SDA-Pad11)") (class "Default")
      (node (ref "IC4") (pin "11") (pinfunction "PIO0_5/SDA_11") (pintype "bidirectional"))
    )
    (net (code "145") (name "unconnected-(IC4-PIO0_16{slash}AD5{slash}CT32B1_MAT3{slash}WAKEUP-Pad26)") (class "Default")
      (node (ref "IC4") (pin "26") (pinfunction "PIO0_16/AD5/CT32B1_MAT3/WAKEUP_26") (pintype "bidirectional"))
    )
    (net (code "146") (name "unconnected-(IC4-PIO0_23{slash}AD7-Pad27)") (class "Default")
      (node (ref "IC4") (pin "27") (pinfunction "PIO0_23/AD7_27") (pintype "bidirectional"))
    )
    (net (code "147") (name "unconnected-(IC4-PIO1_15{slash}~{DCD}{slash}CT16B0_MAT2{slash}SCK1-Pad28)") (class "Default")
      (node (ref "IC4") (pin "28") (pinfunction "PIO1_15/~{DCD}/CT16B0_MAT2/SCK1_28") (pintype "bidirectional"))
    )
    (net (code "148") (name "unconnected-(IC4-SWCLK{slash}PIO0_10{slash}SCK0{slash}CT16B0_MAT2-Pad19)") (class "Default")
      (node (ref "IC4") (pin "19") (pinfunction "SWCLK/PIO0_10/SCK0/CT16B0_MAT2_19") (pintype "bidirectional"))
    )
    (net (code "149") (name "unconnected-(IC4-SWDIO{slash}PIO0_15{slash}AD4{slash}CT32B1_MAT2-Pad25)") (class "Default")
      (node (ref "IC4") (pin "25") (pinfunction "SWDIO/PIO0_15/AD4/CT32B1_MAT2_25") (pintype "bidirectional"))
    )
    (net (code "150") (name "unconnected-(IC4-TDO{slash}PIO0_13{slash}AD2{slash}CT32B1_MAT0-Pad23)") (class "Default")
      (node (ref "IC4") (pin "23") (pinfunction "TDO/PIO0_13/AD2/CT32B1_MAT0_23") (pintype "bidirectional"))
    )
    (net (code "151") (name "unconnected-(IC4-TMS{slash}PIO0_12{slash}AD1{slash}CT32B1_CAP0-Pad22)") (class "Default")
      (node (ref "IC4") (pin "22") (pinfunction "TMS/PIO0_12/AD1/CT32B1_CAP0_22") (pintype "bidirectional"))
    )
    (net (code "152") (name "unconnected-(IC4-~{TRST}{slash}PIO0_14{slash}AD3{slash}CT32B1_MAT1-Pad24)") (class "Default")
      (node (ref "IC4") (pin "24") (pinfunction "~{TRST}/PIO0_14/AD3/CT32B1_MAT1_24") (pintype "bidirectional"))
    )
    (net (code "153") (name "unconnected-(MOD1-CLKM-Pad39)") (class "Default")
      (node (ref "MOD1") (pin "39") (pinfunction "CLKM_39") (pintype "bidirectional"))
    )
    (net (code "154") (name "unconnected-(RESET-EN-Pad3)") (class "Default")
      (node (ref "RESET-EN") (pin "3") (pinfunction "3_3") (pintype "passive"))
    )
  )
)
